# 06_LMS7002M_RF2.net
KiCad netlist of a schematic drawn in Altium Designer
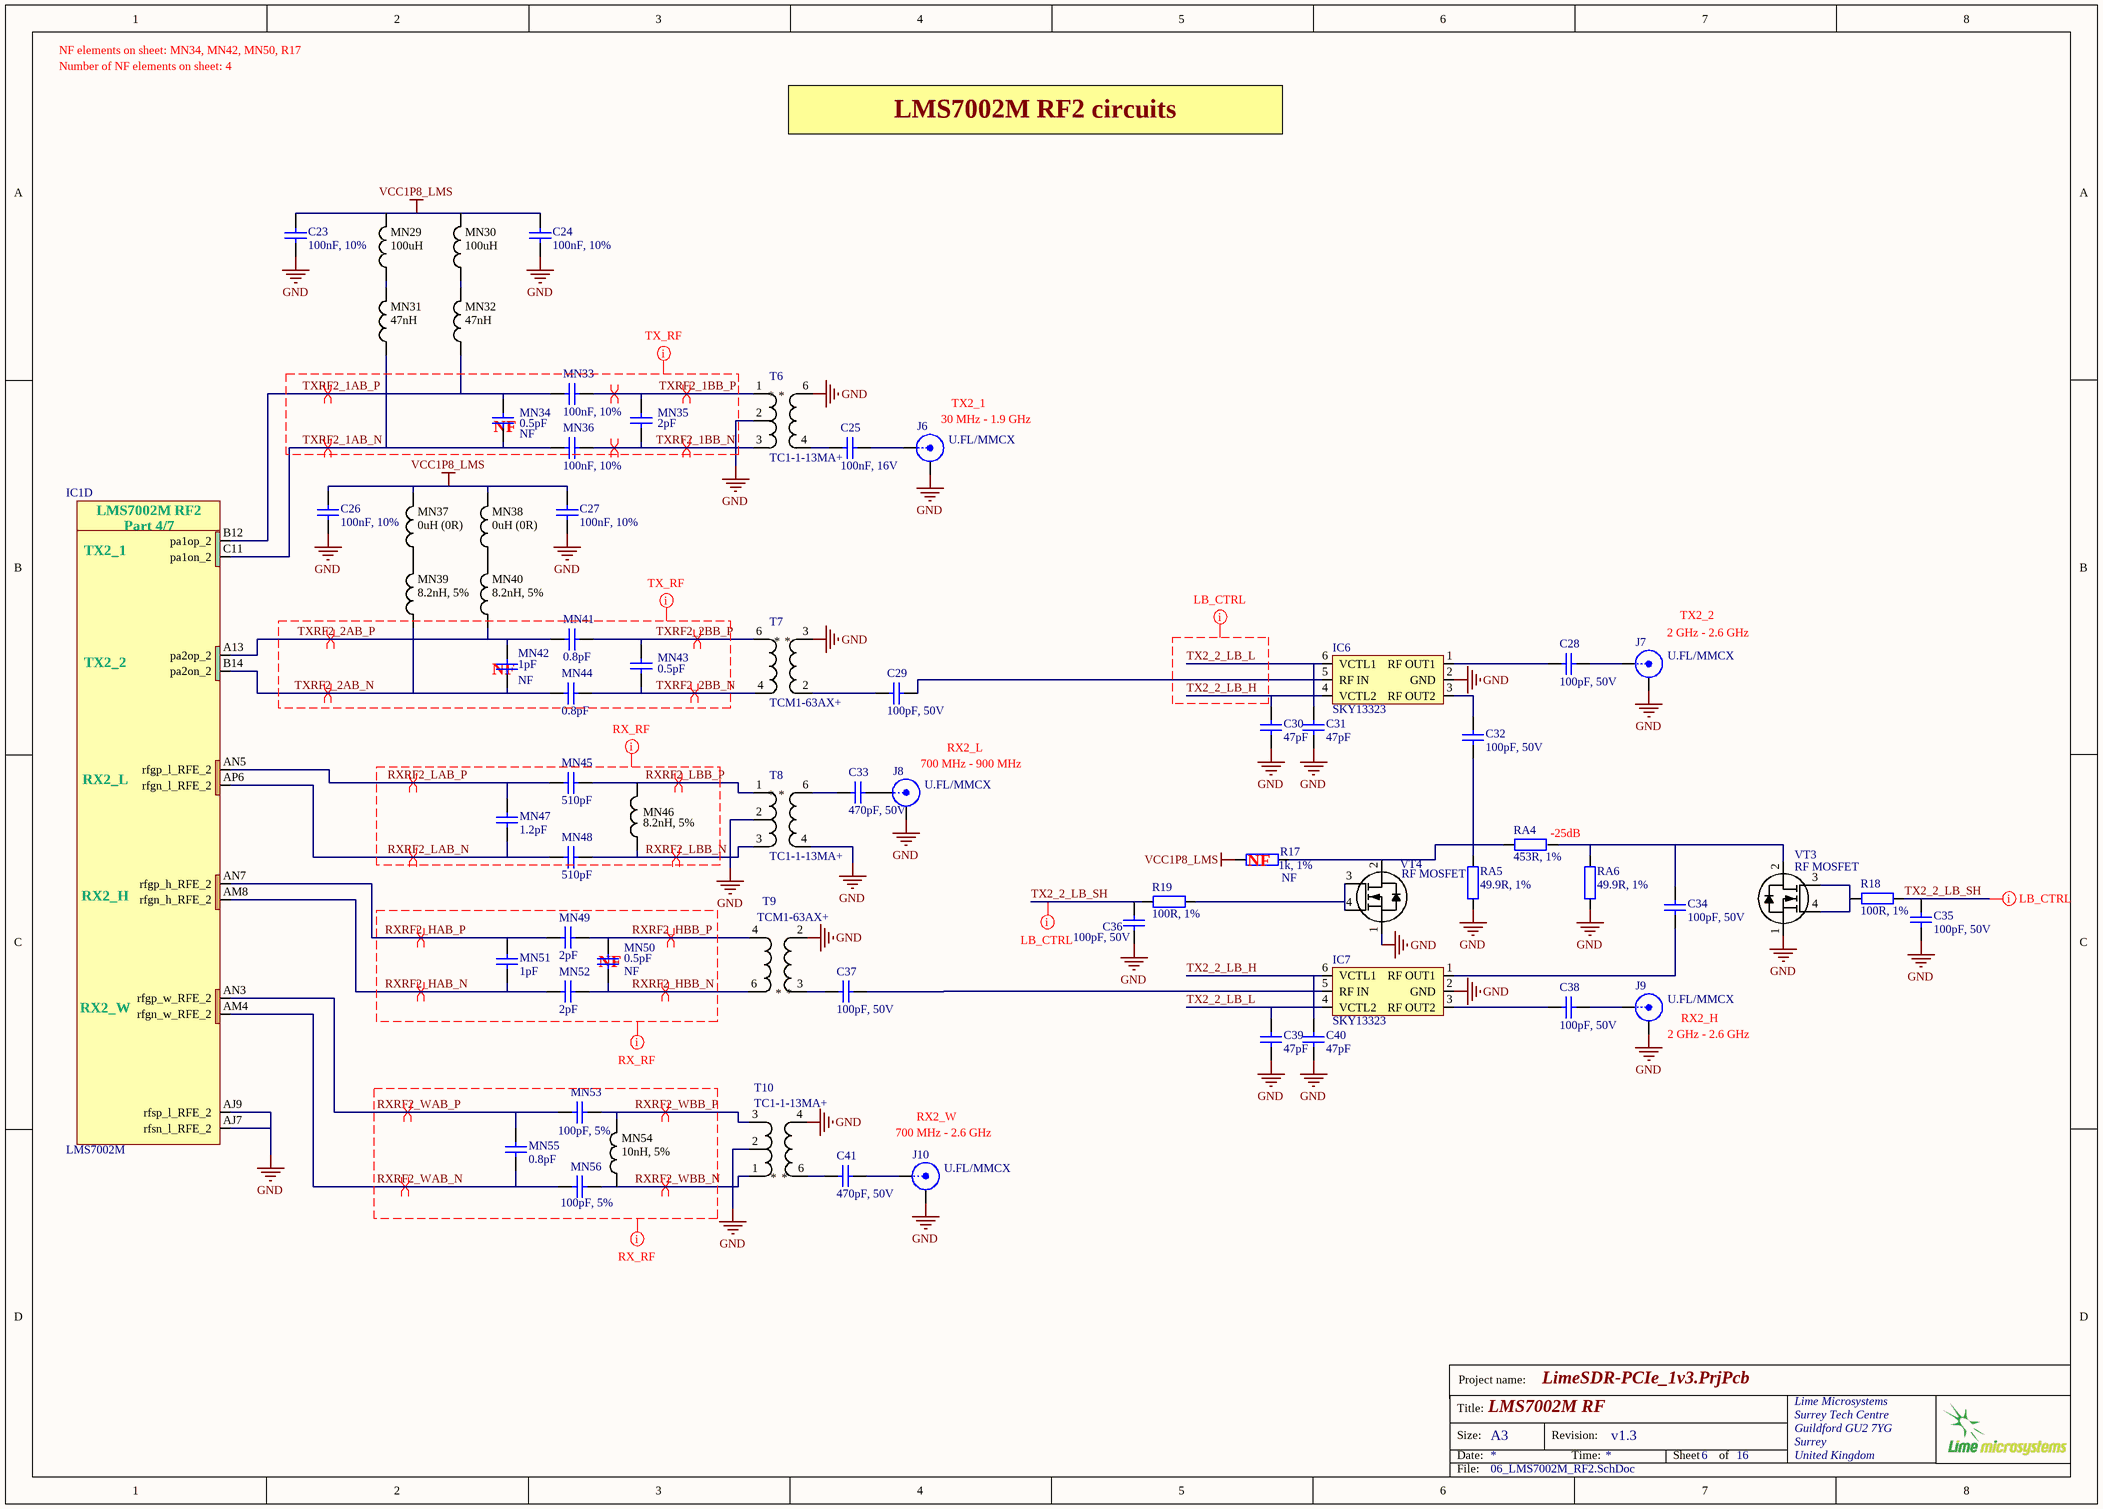
[diagram p0: 06_LMS7002M_RF2.SchDoc]

(export (version "E")
  (design (tool "Eeschema 10.0.6"))
  (components
    (comp (ref "C23")
      (value "100nF, 10%")
      (footprint "CAP0402")
      (fields
        (field (name "MANUFACTURER") "Murata Electronics")
        (field (name "TOLERANCE") "10 %")
        (field (name "MANUFACTURER PART NUMBER") "GRM155R71C104KA88D")
      )
      (libsource (lib "LimeMicroAltiumLib_schLib") (part "Cap_0402"))
    )
    (comp (ref "C24")
      (value "100nF, 10%")
      (footprint "CAP0402")
      (fields
        (field (name "MANUFACTURER") "Murata Electronics")
        (field (name "TOLERANCE") "10 %")
        (field (name "MANUFACTURER PART NUMBER") "GRM155R71C104KA88D")
      )
      (libsource (lib "LimeMicroAltiumLib_schLib") (part "Cap_0402"))
    )
    (comp (ref "C25")
      (value "100nF, 16V")
      (footprint "CAP0402")
      (fields
        (field (name "MANUFACTURER") "Murata Electronics")
        (field (name "TOLERANCE") "10 %")
        (field (name "MANUFACTURER PART NUMBER") "GRM155R71C104KA88D")
      )
      (libsource (lib "LimeMicroAltiumLib_schLib") (part "Cap_0402"))
    )
    (comp (ref "C26")
      (value "100nF, 10%")
      (footprint "CAP0402")
      (fields
        (field (name "MANUFACTURER") "Murata Electronics")
        (field (name "TOLERANCE") "10 %")
        (field (name "MANUFACTURER PART NUMBER") "GRM155R71C104KA88D")
      )
      (libsource (lib "LimeMicroAltiumLib_schLib") (part "Cap_0402"))
    )
    (comp (ref "C27")
      (value "100nF, 10%")
      (footprint "CAP0402")
      (fields
        (field (name "MANUFACTURER") "Murata Electronics")
        (field (name "TOLERANCE") "10 %")
        (field (name "MANUFACTURER PART NUMBER") "GRM155R71C104KA88D")
      )
      (libsource (lib "LimeMicroAltiumLib_schLib") (part "Cap_0402"))
    )
    (comp (ref "C28")
      (value "100pF, 50V")
      (footprint "CAP0402")
      (fields (field (name "TOLERANCE") "±5%") (field (name "MANUFACTURER") "Yageo"))
      (libsource (lib "LimeMicroAltiumLib_schLib") (part "Cap_0402"))
    )
    (comp (ref "C29")
      (value "100pF, 50V")
      (footprint "CAP0402")
      (fields (field (name "TOLERANCE") "±5%") (field (name "MANUFACTURER") "Yageo"))
      (libsource (lib "LimeMicroAltiumLib_schLib") (part "Cap_0402"))
    )
    (comp (ref "C30")
      (value "47pF")
      (footprint "CAP0402")
      (fields (field (name "TOLERANCE") "±1%") (field (name "MANUFACTURER") "TDK Corporation"))
      (libsource (lib "LimeMicroAltiumLib_schLib") (part "Cap_0402"))
    )
    (comp (ref "C31")
      (value "47pF")
      (footprint "CAP0402")
      (fields (field (name "TOLERANCE") "±1%") (field (name "MANUFACTURER") "TDK Corporation"))
      (libsource (lib "LimeMicroAltiumLib_schLib") (part "Cap_0402"))
    )
    (comp (ref "C32")
      (value "100pF, 50V")
      (footprint "CAP0402")
      (fields (field (name "TOLERANCE") "±5%") (field (name "MANUFACTURER") "Yageo"))
      (libsource (lib "LimeMicroAltiumLib_schLib") (part "Cap_0402"))
    )
    (comp (ref "C33")
      (value "470pF, 50V")
      (footprint "CAP0402")
      (fields
        (field (name "MANUFACTURER PART NUMBER") "C1005C0G1H471J050BA")
        (field (name "TOLERANCE") "±5%")
        (field (name "MANUFACTURER") "TDK Corporation")
      )
      (libsource (lib "LimeMicroAltiumLib_schLib") (part "Cap_0402"))
    )
    (comp (ref "C34")
      (value "100pF, 50V")
      (footprint "CAP0402")
      (fields (field (name "TOLERANCE") "±5%") (field (name "MANUFACTURER") "Yageo"))
      (libsource (lib "LimeMicroAltiumLib_schLib") (part "Cap_0402"))
    )
    (comp (ref "C35")
      (value "100pF, 50V")
      (footprint "CAP0402")
      (fields (field (name "TOLERANCE") "±5%") (field (name "MANUFACTURER") "Yageo"))
      (libsource (lib "LimeMicroAltiumLib_schLib") (part "Cap_0402"))
    )
    (comp (ref "C36")
      (value "100pF, 50V")
      (footprint "CAP0402")
      (fields (field (name "TOLERANCE") "±5%") (field (name "MANUFACTURER") "Yageo"))
      (libsource (lib "LimeMicroAltiumLib_schLib") (part "Cap_0402"))
    )
    (comp (ref "C37")
      (value "100pF, 50V")
      (footprint "CAP0402")
      (fields (field (name "TOLERANCE") "±5%") (field (name "MANUFACTURER") "Yageo"))
      (libsource (lib "LimeMicroAltiumLib_schLib") (part "Cap_0402"))
    )
    (comp (ref "C38")
      (value "100pF, 50V")
      (footprint "CAP0402")
      (fields (field (name "TOLERANCE") "±5%") (field (name "MANUFACTURER") "Yageo"))
      (libsource (lib "LimeMicroAltiumLib_schLib") (part "Cap_0402"))
    )
    (comp (ref "C39")
      (value "47pF")
      (footprint "CAP0402")
      (fields (field (name "TOLERANCE") "±1%") (field (name "MANUFACTURER") "TDK Corporation"))
      (libsource (lib "LimeMicroAltiumLib_schLib") (part "Cap_0402"))
    )
    (comp (ref "C40")
      (value "47pF")
      (footprint "CAP0402")
      (fields (field (name "TOLERANCE") "±1%") (field (name "MANUFACTURER") "TDK Corporation"))
      (libsource (lib "LimeMicroAltiumLib_schLib") (part "Cap_0402"))
    )
    (comp (ref "C41")
      (value "470pF, 50V")
      (footprint "CAP0402")
      (fields
        (field (name "MANUFACTURER PART NUMBER") "C1005C0G1H471J050BA")
        (field (name "TOLERANCE") "±5%")
        (field (name "MANUFACTURER") "TDK Corporation")
      )
      (libsource (lib "LimeMicroAltiumLib_schLib") (part "Cap_0402"))
    )
    (comp (ref "IC1")
      (value "LMS7002M")
      (footprint "LMS7002M_v2")
      (description "Schematic symbol revision 3. Default footprint - 0.31mm pad")
      (fields (field (name "MANUFACTURER") "Lime Microsystems"))
      (libsource (lib "LimeMicroAltiumLib_schLib") (part "LMS7002Mr3"))
    )
    (comp (ref "IC6")
      (value "SKY13323")
      (footprint "SKY13323-378LF")
      (description "SKY13323-378LF: 0.1-3.0 GHz GaAs SPDT Switch")
      (fields (field (name "MANUFACTURER") "Skyworks Solutions Inc."))
      (libsource (lib "LimeMicroAltiumLib_schLib") (part "SKY13323"))
    )
    (comp (ref "IC7")
      (value "SKY13323")
      (footprint "SKY13323-378LF")
      (description "SKY13323-378LF: 0.1-3.0 GHz GaAs SPDT Switch")
      (fields (field (name "MANUFACTURER") "Skyworks Solutions Inc."))
      (libsource (lib "LimeMicroAltiumLib_schLib") (part "SKY13323"))
    )
    (comp (ref "J6")
      (value "U.FL/MMCX")
      (footprint "MMCX_UFL_conn_u")
      (description "CONN UMC RCPT STR 50 OHM SMD")
      (fields (field (name "MANUFACTURER") "Molex, LLC"))
      (libsource (lib "LimeMicroAltiumLib_schLib") (part "RF_IF_connector"))
    )
    (comp (ref "J7")
      (value "U.FL/MMCX")
      (footprint "MMCX_UFL_conn_u")
      (description "CONN UMC RCPT STR 50 OHM SMD")
      (fields (field (name "MANUFACTURER") "Molex, LLC"))
      (libsource (lib "LimeMicroAltiumLib_schLib") (part "RF_IF_connector"))
    )
    (comp (ref "J8")
      (value "U.FL/MMCX")
      (footprint "MMCX_UFL_conn_u")
      (description "CONN UMC RCPT STR 50 OHM SMD")
      (fields (field (name "MANUFACTURER") "Molex, LLC"))
      (libsource (lib "LimeMicroAltiumLib_schLib") (part "RF_IF_connector"))
    )
    (comp (ref "J9")
      (value "U.FL/MMCX")
      (footprint "MMCX_UFL_conn_u")
      (description "CONN UMC RCPT STR 50 OHM SMD")
      (fields (field (name "MANUFACTURER") "Molex, LLC"))
      (libsource (lib "LimeMicroAltiumLib_schLib") (part "RF_IF_connector"))
    )
    (comp (ref "J10")
      (value "U.FL/MMCX")
      (footprint "MMCX_UFL_conn_u")
      (description "CONN UMC RCPT STR 50 OHM SMD")
      (fields (field (name "MANUFACTURER") "Molex, LLC"))
      (libsource (lib "LimeMicroAltiumLib_schLib") (part "RF_IF_connector"))
    )
    (comp (ref "MN29")
      (value "100uH")
      (footprint "RES0805")
      (fields
        (field (name "TOLERANCE") "±10%")
        (field (name "MANUFACTURER") "TDK Corporation")
        (field (name "MANUFACTURER PART NUMBER") "MLF2012C101KT000")
      )
      (libsource (lib "LimeMicroAltiumLib_schLib") (part "Inductor_0603"))
    )
    (comp (ref "MN30")
      (value "100uH")
      (footprint "RES0805")
      (fields
        (field (name "TOLERANCE") "±10%")
        (field (name "MANUFACTURER") "TDK Corporation")
        (field (name "MANUFACTURER PART NUMBER") "MLF2012C101KT000")
      )
      (libsource (lib "LimeMicroAltiumLib_schLib") (part "Inductor_0603"))
    )
    (comp (ref "MN31")
      (value "47nH")
      (footprint "RES0402")
      (fields
        (field (name "MANUFACTURER") "COILCRAFT")
        (field (name "MANUFACTURER PART NUMBER") "0402HP-47NXJLU")
      )
      (libsource (lib "LimeMicroAltiumLib_schLib") (part "Inductor_0603"))
    )
    (comp (ref "MN32")
      (value "47nH")
      (footprint "RES0402")
      (fields
        (field (name "MANUFACTURER") "COILCRAFT")
        (field (name "MANUFACTURER PART NUMBER") "0402HP-47NXJLU")
      )
      (libsource (lib "LimeMicroAltiumLib_schLib") (part "Inductor_0603"))
    )
    (comp (ref "MN33")
      (value "100nF, 10%")
      (footprint "CAP0402")
      (fields
        (field (name "MANUFACTURER") "Murata Electronics")
        (field (name "TOLERANCE") "10 %")
        (field (name "MANUFACTURER PART NUMBER") "GRM155R71C104KA88D")
      )
      (libsource (lib "LimeMicroAltiumLib_schLib") (part "Cap_0402"))
    )
    (comp (ref "MN34")
      (value "0.5pF")
      (footprint "CAP0402")
      (fields
        (field (name "ASSEMBLY INFO") "NF")
        (field (name "TOLERANCE") "±0.25pF")
        (field (name "MANUFACTURER") "Yageo")
      )
      (libsource (lib "LimeMicroAltiumLib_schLib") (part "Cap_0402"))
    )
    (comp (ref "MN35")
      (value "2pF")
      (footprint "CAP0402")
      (fields (field (name "MANUFACTURER PART NUMBER") "04025U2R0BAT2A") (field (name "MANUFACTURER") "AVX"))
      (libsource (lib "LimeMicroAltiumLib_schLib") (part "Cap_0402"))
    )
    (comp (ref "MN36")
      (value "100nF, 10%")
      (footprint "CAP0402")
      (fields
        (field (name "MANUFACTURER") "Murata Electronics")
        (field (name "TOLERANCE") "10 %")
        (field (name "MANUFACTURER PART NUMBER") "GRM155R71C104KA88D")
      )
      (libsource (lib "LimeMicroAltiumLib_schLib") (part "Cap_0402"))
    )
    (comp (ref "MN37")
      (value "0uH (0R)")
      (footprint "RES0805")
      (fields
        (field (name "MANUFACTURER") "BOURNS")
        (field (name "MANUFACTURER PART NUMBER") "CR0805-J/-000ELF")
      )
      (libsource (lib "LimeMicroAltiumLib_schLib") (part "Inductor_0603"))
    )
    (comp (ref "MN38")
      (value "0uH (0R)")
      (footprint "RES0805")
      (fields
        (field (name "MANUFACTURER") "BOURNS")
        (field (name "MANUFACTURER PART NUMBER") "CR0805-J/-000ELF")
      )
      (libsource (lib "LimeMicroAltiumLib_schLib") (part "Inductor_0603"))
    )
    (comp (ref "MN39")
      (value "8.2nH, 5%")
      (footprint "RES0402")
      (fields (field (name "MANUFACTURER") "COILCRAFT"))
      (libsource (lib "LimeMicroAltiumLib_schLib") (part "Inductor_0603"))
    )
    (comp (ref "MN40")
      (value "8.2nH, 5%")
      (footprint "RES0402")
      (fields (field (name "MANUFACTURER") "COILCRAFT"))
      (libsource (lib "LimeMicroAltiumLib_schLib") (part "Inductor_0603"))
    )
    (comp (ref "MN41")
      (value "0.8pF")
      (footprint "CAP0402")
      (fields
        (field (name "TOLERANCE") "±0.1pF")
        (field (name "MANUFACTURER") "Murata Electronics North America")
        (field (name "MANUFACTURER PART NUMBER") "GRM1555C1HR80BA01D")
      )
      (libsource (lib "LimeMicroAltiumLib_schLib") (part "Cap_0402"))
    )
    (comp (ref "MN42")
      (value "1pF")
      (footprint "CAP0402")
      (fields
        (field (name "ASSEMBLY INFO") "NF")
        (field (name "MANUFACTURER") "TDK Corporation")
        (field (name "TOLERANCE") "±0.1pF")
      )
      (libsource (lib "LimeMicroAltiumLib_schLib") (part "Cap_0402"))
    )
    (comp (ref "MN43")
      (value "0.5pF")
      (footprint "CAP0402")
      (fields (field (name "TOLERANCE") "±0.25pF") (field (name "MANUFACTURER") "Yageo"))
      (libsource (lib "LimeMicroAltiumLib_schLib") (part "Cap_0402"))
    )
    (comp (ref "MN44")
      (value "0.8pF")
      (footprint "CAP0402")
      (fields
        (field (name "TOLERANCE") "±0.1pF")
        (field (name "MANUFACTURER") "Murata Electronics North America")
        (field (name "MANUFACTURER PART NUMBER") "GRM1555C1HR80BA01D")
      )
      (libsource (lib "LimeMicroAltiumLib_schLib") (part "Cap_0402"))
    )
    (comp (ref "MN45")
      (value "510pF")
      (footprint "CAP0402")
      (fields
        (field (name "TOLERANCE") "±5%")
        (field (name "MANUFACTURER") "Murata Electronics North America")
        (field (name "MANUFACTURER PART NUMBER") "GRM1555C1H511JA01D")
      )
      (libsource (lib "LimeMicroAltiumLib_schLib") (part "Cap_0402"))
    )
    (comp (ref "MN46")
      (value "8.2nH, 5%")
      (footprint "RES0402")
      (fields (field (name "MANUFACTURER") "COILCRAFT"))
      (libsource (lib "LimeMicroAltiumLib_schLib") (part "Inductor_0603"))
    )
    (comp (ref "MN47")
      (value "1.2pF")
      (footprint "CAP0402")
      (fields
        (field (name "MANUFACTURER") "Murata Electronics North America")
        (field (name "MANUFACTURER PART NUMBER") "GRM1555C1H1R2CA01D")
        (field (name "TOLERANCE") "±0.25pF")
      )
      (libsource (lib "LimeMicroAltiumLib_schLib") (part "Cap_0402"))
    )
    (comp (ref "MN48")
      (value "510pF")
      (footprint "CAP0402")
      (fields
        (field (name "TOLERANCE") "±5%")
        (field (name "MANUFACTURER") "Murata Electronics North America")
        (field (name "MANUFACTURER PART NUMBER") "GRM1555C1H511JA01D")
      )
      (libsource (lib "LimeMicroAltiumLib_schLib") (part "Cap_0402"))
    )
    (comp (ref "MN49")
      (value "2pF")
      (footprint "CAP0402")
      (fields (field (name "MANUFACTURER PART NUMBER") "04025U2R0BAT2A") (field (name "MANUFACTURER") "AVX"))
      (libsource (lib "LimeMicroAltiumLib_schLib") (part "Cap_0402"))
    )
    (comp (ref "MN50")
      (value "0.5pF")
      (footprint "CAP0402")
      (fields
        (field (name "ASSEMBLY INFO") "NF")
        (field (name "TOLERANCE") "±0.25pF")
        (field (name "MANUFACTURER") "Yageo")
      )
      (libsource (lib "LimeMicroAltiumLib_schLib") (part "Cap_0402"))
    )
    (comp (ref "MN51")
      (value "1pF")
      (footprint "CAP0402")
      (fields (field (name "MANUFACTURER") "TDK Corporation") (field (name "TOLERANCE") "±0.1pF"))
      (libsource (lib "LimeMicroAltiumLib_schLib") (part "Cap_0402"))
    )
    (comp (ref "MN52")
      (value "2pF")
      (footprint "CAP0402")
      (fields (field (name "MANUFACTURER PART NUMBER") "04025U2R0BAT2A") (field (name "MANUFACTURER") "AVX"))
      (libsource (lib "LimeMicroAltiumLib_schLib") (part "Cap_0402"))
    )
    (comp (ref "MN53")
      (value "100pF, 5%")
      (footprint "CAP0402")
      (fields (field (name "TOLERANCE") "±5%") (field (name "MANUFACTURER") "Yageo"))
      (libsource (lib "LimeMicroAltiumLib_schLib") (part "Cap_0402"))
    )
    (comp (ref "MN54")
      (value "10nH, 5%")
      (footprint "RES0402")
      (fields (field (name "MANUFACTURER") "COILCRAFT"))
      (libsource (lib "LimeMicroAltiumLib_schLib") (part "Inductor_0603"))
    )
    (comp (ref "MN55")
      (value "0.8pF")
      (footprint "CAP0402")
      (fields
        (field (name "TOLERANCE") "±0.1pF")
        (field (name "MANUFACTURER") "Murata Electronics North America")
        (field (name "MANUFACTURER PART NUMBER") "GRM1555C1HR80BA01D")
      )
      (libsource (lib "LimeMicroAltiumLib_schLib") (part "Cap_0402"))
    )
    (comp (ref "MN56")
      (value "100pF, 5%")
      (footprint "CAP0402")
      (fields (field (name "TOLERANCE") "±5%") (field (name "MANUFACTURER") "Yageo"))
      (libsource (lib "LimeMicroAltiumLib_schLib") (part "Cap_0402"))
    )
    (comp (ref "R17")
      (value "1k, 1%")
      (footprint "RES0402")
      (fields
        (field (name "ASSEMBLY INFO") "NF")
        (field (name "MANUFACTURER") "Stackpole Electronics Inc")
        (field (name "TOLERANCE") "±1%")
      )
      (libsource (lib "LimeMicroAltiumLib_schLib") (part "Res_0402"))
    )
    (comp (ref "R18")
      (value "100R, 1%")
      (footprint "RES0402")
      (fields (field (name "TOLERANCE") "±1%") (field (name "MANUFACTURER") "Stackpole Electronics Inc."))
      (libsource (lib "LimeFPGAboard_schLib") (part "Res_0402"))
    )
    (comp (ref "R19")
      (value "100R, 1%")
      (footprint "RES0402")
      (fields (field (name "TOLERANCE") "±1%") (field (name "MANUFACTURER") "Stackpole Electronics Inc."))
      (libsource (lib "LimeFPGAboard_schLib") (part "Res_0402"))
    )
    (comp (ref "RA4")
      (value "453R, 1%")
      (footprint "RES0402")
      (fields (field (name "MANUFACTURER") "Yageo") (field (name "TOLERANCE") "±1%"))
      (libsource (lib "LimeMicroAltiumLib_schLib") (part "Res_0402"))
    )
    (comp (ref "RA5")
      (value "49.9R, 1%")
      (footprint "RES0402")
      (fields
        (field (name "TOLERANCE") "±1%")
        (field (name "MANUFACTURER") "Samsung Electro-Mechanics America, Inc.")
        (field (name "MANUFACTURER PART NUMBER") "RC1005F49R9CS")
      )
      (libsource (lib "LimeMicroAltiumLib_schLib") (part "Res_0402"))
    )
    (comp (ref "RA6")
      (value "49.9R, 1%")
      (footprint "RES0402")
      (fields
        (field (name "TOLERANCE") "±1%")
        (field (name "MANUFACTURER") "Samsung Electro-Mechanics America, Inc.")
        (field (name "MANUFACTURER PART NUMBER") "RC1005F49R9CS")
      )
      (libsource (lib "LimeMicroAltiumLib_schLib") (part "Res_0402"))
    )
    (comp (ref "T6")
      (value "TC1-1-13MA+")
      (footprint "TC1-1-13MA+_v2")
      (fields (field (name "MANUFACTURER") "Mini-Circuits"))
      (libsource (lib "LimeMicroAltiumLib_schLib") (part "Balun"))
    )
    (comp (ref "T7")
      (value "TCM1-63AX+")
      (footprint "TCM1-63AX+_v2")
      (fields (field (name "MANUFACTURER") "Mini-circuits"))
      (libsource (lib "LimeMicroAltiumLib_schLib") (part "Balun_v2"))
    )
    (comp (ref "T8")
      (value "TC1-1-13MA+")
      (footprint "TC1-1-13MA+_v2")
      (fields (field (name "MANUFACTURER") "Mini-Circuits"))
      (libsource (lib "LimeMicroAltiumLib_schLib") (part "Balun"))
    )
    (comp (ref "T9")
      (value "TCM1-63AX+")
      (footprint "TCM1-63AX+_v2")
      (fields (field (name "MANUFACTURER") "Mini-circuits"))
      (libsource (lib "") (part "Balun_v2_1"))
    )
    (comp (ref "T10")
      (value "TC1-1-13MA+")
      (footprint "TC1-1-13MA+_v2")
      (fields (field (name "MANUFACTURER") "Mini-Circuits"))
      (libsource (lib "") (part "Balun_1"))
    )
    (comp (ref "VT3")
      (value "RF MOSFET")
      (footprint "BF1105R_SOT143R4")
      (fields (field (name "MANUFACTURER") "NXP Semiconductors"))
      (libsource (lib "LimeMicroAltiumLib_schLib") (part "BF1105R,215"))
    )
    (comp (ref "VT4")
      (value "RF MOSFET")
      (footprint "BF1105R_SOT143R4")
      (fields (field (name "MANUFACTURER") "NXP Semiconductors"))
      (libsource (lib "LimeMicroAltiumLib_schLib") (part "BF1105R,215"))
    )
  )
  (nets
    (net (code "1") (name "/RXRF2_HAB_N") (class "Default")
      (node (ref "IC1") (pin "AM8") (pinfunction "rfgn_h_RFE_2_AM8") (pintype "passive"))
      (node (ref "MN51") (pin "1") (pinfunction "1_1") (pintype "passive"))
      (node (ref "MN52") (pin "2") (pinfunction "2_2") (pintype "passive"))
    )
    (net (code "2") (name "/RXRF2_HAB_P") (class "Default")
      (node (ref "IC1") (pin "AN7") (pinfunction "rfgp_h_RFE_2_AN7") (pintype "passive"))
      (node (ref "MN49") (pin "2") (pinfunction "2_2") (pintype "passive"))
      (node (ref "MN51") (pin "2") (pinfunction "2_2") (pintype "passive"))
    )
    (net (code "3") (name "/RXRF2_HBB_N") (class "Default")
      (node (ref "MN50") (pin "1") (pinfunction "1_1") (pintype "passive"))
      (node (ref "MN52") (pin "1") (pinfunction "1_1") (pintype "passive"))
      (node (ref "T9") (pin "6") (pinfunction "6_6") (pintype "passive"))
    )
    (net (code "4") (name "/RXRF2_HBB_P") (class "Default")
      (node (ref "MN49") (pin "1") (pinfunction "1_1") (pintype "passive"))
      (node (ref "MN50") (pin "2") (pinfunction "2_2") (pintype "passive"))
      (node (ref "T9") (pin "4") (pinfunction "4_4") (pintype "passive"))
    )
    (net (code "5") (name "/RXRF2_LAB_N") (class "Default")
      (node (ref "IC1") (pin "AP6") (pinfunction "rfgn_l_RFE_2_AP6") (pintype "passive"))
      (node (ref "MN47") (pin "1") (pinfunction "1_1") (pintype "passive"))
      (node (ref "MN48") (pin "2") (pinfunction "2_2") (pintype "passive"))
    )
    (net (code "6") (name "/RXRF2_LAB_P") (class "Default")
      (node (ref "IC1") (pin "AN5") (pinfunction "rfgp_l_RFE_2_AN5") (pintype "passive"))
      (node (ref "MN45") (pin "2") (pinfunction "2_2") (pintype "passive"))
      (node (ref "MN47") (pin "2") (pinfunction "2_2") (pintype "passive"))
    )
    (net (code "7") (name "/RXRF2_LBB_N") (class "Default")
      (node (ref "MN46") (pin "1") (pinfunction "1_1") (pintype "passive"))
      (node (ref "MN48") (pin "1") (pinfunction "1_1") (pintype "passive"))
      (node (ref "T8") (pin "3") (pinfunction "3_3") (pintype "passive"))
    )
    (net (code "8") (name "/RXRF2_LBB_P") (class "Default")
      (node (ref "MN45") (pin "1") (pinfunction "1_1") (pintype "passive"))
      (node (ref "MN46") (pin "2") (pinfunction "2_2") (pintype "passive"))
      (node (ref "T8") (pin "1") (pinfunction "1_1") (pintype "passive"))
    )
    (net (code "9") (name "/RXRF2_WAB_N") (class "Default")
      (node (ref "IC1") (pin "AM4") (pinfunction "rfgn_w_RFE_2_AM4") (pintype "passive"))
      (node (ref "MN55") (pin "2") (pinfunction "2_2") (pintype "passive"))
      (node (ref "MN56") (pin "2") (pinfunction "2_2") (pintype "passive"))
    )
    (net (code "10") (name "/RXRF2_WAB_P") (class "Default")
      (node (ref "IC1") (pin "AN3") (pinfunction "rfgp_w_RFE_2_AN3") (pintype "passive"))
      (node (ref "MN53") (pin "2") (pinfunction "2_2") (pintype "passive"))
      (node (ref "MN55") (pin "1") (pinfunction "1_1") (pintype "passive"))
    )
    (net (code "11") (name "/RXRF2_WBB_N") (class "Default")
      (node (ref "MN54") (pin "1") (pinfunction "1_1") (pintype "passive"))
      (node (ref "MN56") (pin "1") (pinfunction "1_1") (pintype "passive"))
      (node (ref "T10") (pin "1") (pinfunction "1_1") (pintype "passive"))
    )
    (net (code "12") (name "/RXRF2_WBB_P") (class "Default")
      (node (ref "MN53") (pin "1") (pinfunction "1_1") (pintype "passive"))
      (node (ref "MN54") (pin "2") (pinfunction "2_2") (pintype "passive"))
      (node (ref "T10") (pin "3") (pinfunction "3_3") (pintype "passive"))
    )
    (net (code "13") (name "/TX2_2_LB_H") (class "Default")
      (node (ref "C30") (pin "2") (pinfunction "2_2") (pintype "passive"))
      (node (ref "C40") (pin "2") (pinfunction "2_2") (pintype "passive"))
      (node (ref "IC6") (pin "4") (pinfunction "VCTL2_4") (pintype "input"))
      (node (ref "IC7") (pin "6") (pinfunction "VCTL1_6") (pintype "input"))
    )
    (net (code "14") (name "/TX2_2_LB_L") (class "Default")
      (node (ref "C31") (pin "2") (pinfunction "2_2") (pintype "passive"))
      (node (ref "C39") (pin "2") (pinfunction "2_2") (pintype "passive"))
      (node (ref "IC6") (pin "6") (pinfunction "VCTL1_6") (pintype "input"))
      (node (ref "IC7") (pin "4") (pinfunction "VCTL2_4") (pintype "input"))
    )
    (net (code "15") (name "/TX2_2_LB_SH") (class "Default")
      (node (ref "C35") (pin "1") (pinfunction "1_1") (pintype "passive"))
      (node (ref "C36") (pin "1") (pinfunction "1_1") (pintype "passive"))
      (node (ref "R18") (pin "1") (pinfunction "1_1") (pintype "passive"))
      (node (ref "R19") (pin "2") (pinfunction "2_2") (pintype "passive"))
    )
    (net (code "16") (name "/TXRF2_1AB_N") (class "Default")
      (node (ref "IC1") (pin "C11") (pinfunction "pa1on_2_C11") (pintype "passive"))
      (node (ref "MN31") (pin "1") (pinfunction "1_1") (pintype "passive"))
      (node (ref "MN34") (pin "1") (pinfunction "1_1") (pintype "passive"))
      (node (ref "MN36") (pin "1") (pinfunction "1_1") (pintype "passive"))
    )
    (net (code "17") (name "/TXRF2_1AB_P") (class "Default")
      (node (ref "IC1") (pin "B12") (pinfunction "pa1op_2_B12") (pintype "passive"))
      (node (ref "MN32") (pin "1") (pinfunction "1_1") (pintype "passive"))
      (node (ref "MN33") (pin "2") (pinfunction "2_2") (pintype "passive"))
      (node (ref "MN34") (pin "2") (pinfunction "2_2") (pintype "passive"))
    )
    (net (code "18") (name "/TXRF2_1BB_N") (class "Default")
      (node (ref "MN35") (pin "1") (pinfunction "1_1") (pintype "passive"))
      (node (ref "MN36") (pin "2") (pinfunction "2_2") (pintype "passive"))
      (node (ref "T6") (pin "3") (pinfunction "3_3") (pintype "passive"))
    )
    (net (code "19") (name "/TXRF2_1BB_P") (class "Default")
      (node (ref "MN33") (pin "1") (pinfunction "1_1") (pintype "passive"))
      (node (ref "MN35") (pin "2") (pinfunction "2_2") (pintype "passive"))
      (node (ref "T6") (pin "1") (pinfunction "1_1") (pintype "passive"))
    )
    (net (code "20") (name "/TXRF2_2AB_N") (class "Default")
      (node (ref "IC1") (pin "B14") (pinfunction "pa2on_2_B14") (pintype "passive"))
      (node (ref "MN39") (pin "1") (pinfunction "1_1") (pintype "passive"))
      (node (ref "MN42") (pin "2") (pinfunction "2_2") (pintype "passive"))
      (node (ref "MN44") (pin "2") (pinfunction "2_2") (pintype "passive"))
    )
    (net (code "21") (name "/TXRF2_2AB_P") (class "Default")
      (node (ref "IC1") (pin "A13") (pinfunction "pa2op_2_A13") (pintype "passive"))
      (node (ref "MN40") (pin "1") (pinfunction "1_1") (pintype "passive"))
      (node (ref "MN41") (pin "2") (pinfunction "2_2") (pintype "passive"))
      (node (ref "MN42") (pin "1") (pinfunction "1_1") (pintype "passive"))
    )
    (net (code "22") (name "/TXRF2_2BB_N") (class "Default")
      (node (ref "MN43") (pin "1") (pinfunction "1_1") (pintype "passive"))
      (node (ref "MN44") (pin "1") (pinfunction "1_1") (pintype "passive"))
      (node (ref "T7") (pin "4") (pinfunction "4_4") (pintype "passive"))
    )
    (net (code "23") (name "/TXRF2_2BB_P") (class "Default")
      (node (ref "MN41") (pin "1") (pinfunction "1_1") (pintype "passive"))
      (node (ref "MN43") (pin "2") (pinfunction "2_2") (pintype "passive"))
      (node (ref "T7") (pin "6") (pinfunction "6_6") (pintype "passive"))
    )
    (net (code "24") (name "GND") (class "Default")
      (node (ref "C23") (pin "1") (pinfunction "1_1") (pintype "passive"))
      (node (ref "C24") (pin "1") (pinfunction "1_1") (pintype "passive"))
      (node (ref "C26") (pin "1") (pinfunction "1_1") (pintype "passive"))
      (node (ref "C27") (pin "1") (pinfunction "1_1") (pintype "passive"))
      (node (ref "C30") (pin "1") (pinfunction "1_1") (pintype "passive"))
      (node (ref "C31") (pin "1") (pinfunction "1_1") (pintype "passive"))
      (node (ref "C35") (pin "2") (pinfunction "2_2") (pintype "passive"))
      (node (ref "C36") (pin "2") (pinfunction "2_2") (pintype "passive"))
      (node (ref "C39") (pin "1") (pinfunction "1_1") (pintype "passive"))
      (node (ref "C40") (pin "1") (pinfunction "1_1") (pintype "passive"))
      (node (ref "IC1") (pin "AJ7") (pinfunction "rfsn_l_RFE_2_AJ7") (pintype "passive"))
      (node (ref "IC1") (pin "AJ9") (pinfunction "rfsp_l_RFE_2_AJ9") (pintype "passive"))
      (node (ref "IC6") (pin "2") (pinfunction "GND_2") (pintype "passive"))
      (node (ref "IC7") (pin "2") (pinfunction "GND_2") (pintype "passive"))
      (node (ref "J10") (pin "2") (pinfunction "Y_2") (pintype "passive"))
      (node (ref "J6") (pin "2") (pinfunction "Y_2") (pintype "passive"))
      (node (ref "J7") (pin "2") (pinfunction "Y_2") (pintype "passive"))
      (node (ref "J8") (pin "2") (pinfunction "Y_2") (pintype "passive"))
      (node (ref "J9") (pin "2") (pinfunction "Y_2") (pintype "passive"))
      (node (ref "RA5") (pin "1") (pinfunction "1_1") (pintype "passive"))
      (node (ref "RA6") (pin "1") (pinfunction "1_1") (pintype "passive"))
      (node (ref "T10") (pin "2") (pinfunction "2_2") (pintype "passive"))
      (node (ref "T10") (pin "4") (pinfunction "4_4") (pintype "passive"))
      (node (ref "T6") (pin "2") (pinfunction "2_2") (pintype "passive"))
      (node (ref "T6") (pin "6") (pinfunction "6_6") (pintype "passive"))
      (node (ref "T7") (pin "3") (pinfunction "3_3") (pintype "passive"))
      (node (ref "T8") (pin "2") (pinfunction "2_2") (pintype "passive"))
      (node (ref "T8") (pin "4") (pinfunction "4_4") (pintype "passive"))
      (node (ref "T9") (pin "2") (pinfunction "2_2") (pintype "passive"))
      (node (ref "VT3") (pin "1") (pinfunction "S_1") (pintype "passive"))
      (node (ref "VT4") (pin "1") (pinfunction "S_1") (pintype "passive"))
    )
    (net (code "25") (name "Net-(C25-Pad2)") (class "Default")
      (node (ref "C25") (pin "2") (pinfunction "2_2") (pintype "passive"))
      (node (ref "T6") (pin "4") (pinfunction "4_4") (pintype "passive"))
    )
    (net (code "26") (name "Net-(C29-Pad2)") (class "Default")
      (node (ref "C29") (pin "2") (pinfunction "2_2") (pintype "passive"))
      (node (ref "T7") (pin "2") (pinfunction "2_2") (pintype "passive"))
    )
    (net (code "27") (name "Net-(C33-Pad2)") (class "Default")
      (node (ref "C33") (pin "2") (pinfunction "2_2") (pintype "passive"))
      (node (ref "T8") (pin "6") (pinfunction "6_6") (pintype "passive"))
    )
    (net (code "28") (name "Net-(C37-Pad2)") (class "Default")
      (node (ref "C37") (pin "2") (pinfunction "2_2") (pintype "passive"))
      (node (ref "T9") (pin "3") (pinfunction "3_3") (pintype "passive"))
    )
    (net (code "29") (name "Net-(C41-Pad2)") (class "Default")
      (node (ref "C41") (pin "2") (pinfunction "2_2") (pintype "passive"))
      (node (ref "T10") (pin "6") (pinfunction "6_6") (pintype "passive"))
    )
    (net (code "30") (name "Net-(IC6-RF_IN)") (class "Default")
      (node (ref "C29") (pin "1") (pinfunction "1_1") (pintype "passive"))
      (node (ref "IC6") (pin "5") (pinfunction "RF_IN_5") (pintype "input"))
    )
    (net (code "31") (name "Net-(IC6-RF_OUT1)") (class "Default")
      (node (ref "C28") (pin "2") (pinfunction "2_2") (pintype "passive"))
      (node (ref "IC6") (pin "1") (pinfunction "RF_OUT1_1") (pintype "output"))
    )
    (net (code "32") (name "Net-(IC6-RF_OUT2)") (class "Default")
      (node (ref "C32") (pin "1") (pinfunction "1_1") (pintype "passive"))
      (node (ref "IC6") (pin "3") (pinfunction "RF_OUT2_3") (pintype "output"))
    )
    (net (code "33") (name "Net-(IC7-RF_IN)") (class "Default")
      (node (ref "C37") (pin "1") (pinfunction "1_1") (pintype "passive"))
      (node (ref "IC7") (pin "5") (pinfunction "RF_IN_5") (pintype "input"))
    )
    (net (code "34") (name "Net-(IC7-RF_OUT1)") (class "Default")
      (node (ref "C34") (pin "2") (pinfunction "2_2") (pintype "passive"))
      (node (ref "IC7") (pin "1") (pinfunction "RF_OUT1_1") (pintype "output"))
    )
    (net (code "35") (name "Net-(IC7-RF_OUT2)") (class "Default")
      (node (ref "C38") (pin "2") (pinfunction "2_2") (pintype "passive"))
      (node (ref "IC7") (pin "3") (pinfunction "RF_OUT2_3") (pintype "output"))
    )
    (net (code "36") (name "Net-(J6-X)") (class "Default")
      (node (ref "C25") (pin "1") (pinfunction "1_1") (pintype "passive"))
      (node (ref "J6") (pin "1") (pinfunction "X_1") (pintype "passive"))
    )
    (net (code "37") (name "Net-(J7-X)") (class "Default")
      (node (ref "C28") (pin "1") (pinfunction "1_1") (pintype "passive"))
      (node (ref "J7") (pin "1") (pinfunction "X_1") (pintype "passive"))
    )
    (net (code "38") (name "Net-(J8-X)") (class "Default")
      (node (ref "C33") (pin "1") (pinfunction "1_1") (pintype "passive"))
      (node (ref "J8") (pin "1") (pinfunction "X_1") (pintype "passive"))
    )
    (net (code "39") (name "Net-(J9-X)") (class "Default")
      (node (ref "C38") (pin "1") (pinfunction "1_1") (pintype "passive"))
      (node (ref "J9") (pin "1") (pinfunction "X_1") (pintype "passive"))
    )
    (net (code "40") (name "Net-(J10-X)") (class "Default")
      (node (ref "C41") (pin "1") (pinfunction "1_1") (pintype "passive"))
      (node (ref "J10") (pin "1") (pinfunction "X_1") (pintype "passive"))
    )
    (net (code "41") (name "Net-(MN29-Pad1)") (class "Default")
      (node (ref "MN29") (pin "1") (pinfunction "1_1") (pintype "passive"))
      (node (ref "MN31") (pin "2") (pinfunction "2_2") (pintype "passive"))
    )
    (net (code "42") (name "Net-(MN30-Pad1)") (class "Default")
      (node (ref "MN30") (pin "1") (pinfunction "1_1") (pintype "passive"))
      (node (ref "MN32") (pin "2") (pinfunction "2_2") (pintype "passive"))
    )
    (net (code "43") (name "Net-(MN37-Pad1)") (class "Default")
      (node (ref "MN37") (pin "1") (pinfunction "1_1") (pintype "passive"))
      (node (ref "MN39") (pin "2") (pinfunction "2_2") (pintype "passive"))
    )
    (net (code "44") (name "Net-(MN38-Pad1)") (class "Default")
      (node (ref "MN38") (pin "1") (pinfunction "1_1") (pintype "passive"))
      (node (ref "MN40") (pin "2") (pinfunction "2_2") (pintype "passive"))
    )
    (net (code "45") (name "Net-(VT3-D)") (class "Default")
      (node (ref "C34") (pin "1") (pinfunction "1_1") (pintype "passive"))
      (node (ref "RA4") (pin "2") (pinfunction "2_2") (pintype "passive"))
      (node (ref "RA6") (pin "2") (pinfunction "2_2") (pintype "passive"))
      (node (ref "VT3") (pin "2") (pinfunction "D_2") (pintype "passive"))
    )
    (net (code "46") (name "Net-(VT3-G1)") (class "Default")
      (node (ref "R18") (pin "2") (pinfunction "2_2") (pintype "passive"))
      (node (ref "VT3") (pin "3") (pinfunction "G2_3") (pintype "passive"))
      (node (ref "VT3") (pin "4") (pinfunction "G1_4") (pintype "passive"))
    )
    (net (code "47") (name "Net-(VT4-D)") (class "Default")
      (node (ref "C32") (pin "2") (pinfunction "2_2") (pintype "passive"))
      (node (ref "R17") (pin "1") (pinfunction "1_1") (pintype "passive"))
      (node (ref "RA4") (pin "1") (pinfunction "1_1") (pintype "passive"))
      (node (ref "RA5") (pin "2") (pinfunction "2_2") (pintype "passive"))
      (node (ref "VT4") (pin "2") (pinfunction "D_2") (pintype "passive"))
    )
    (net (code "48") (name "Net-(VT4-G1)") (class "Default")
      (node (ref "R19") (pin "1") (pinfunction "1_1") (pintype "passive"))
      (node (ref "VT4") (pin "3") (pinfunction "G2_3") (pintype "passive"))
      (node (ref "VT4") (pin "4") (pinfunction "G1_4") (pintype "passive"))
    )
    (net (code "49") (name "VCC1P8_LMS") (class "Default")
      (node (ref "C23") (pin "2") (pinfunction "2_2") (pintype "passive"))
      (node (ref "C24") (pin "2") (pinfunction "2_2") (pintype "passive"))
      (node (ref "C26") (pin "2") (pinfunction "2_2") (pintype "passive"))
      (node (ref "C27") (pin "2") (pinfunction "2_2") (pintype "passive"))
      (node (ref "MN29") (pin "2") (pinfunction "2_2") (pintype "passive"))
      (node (ref "MN30") (pin "2") (pinfunction "2_2") (pintype "passive"))
      (node (ref "MN37") (pin "2") (pinfunction "2_2") (pintype "passive"))
      (node (ref "MN38") (pin "2") (pinfunction "2_2") (pintype "passive"))
      (node (ref "R17") (pin "2") (pinfunction "2_2") (pintype "passive"))
    )
  )
)
